# SH-SwitchNode-CT1_Shield.net
KiCad netlist of a schematic drawn in EAGLE
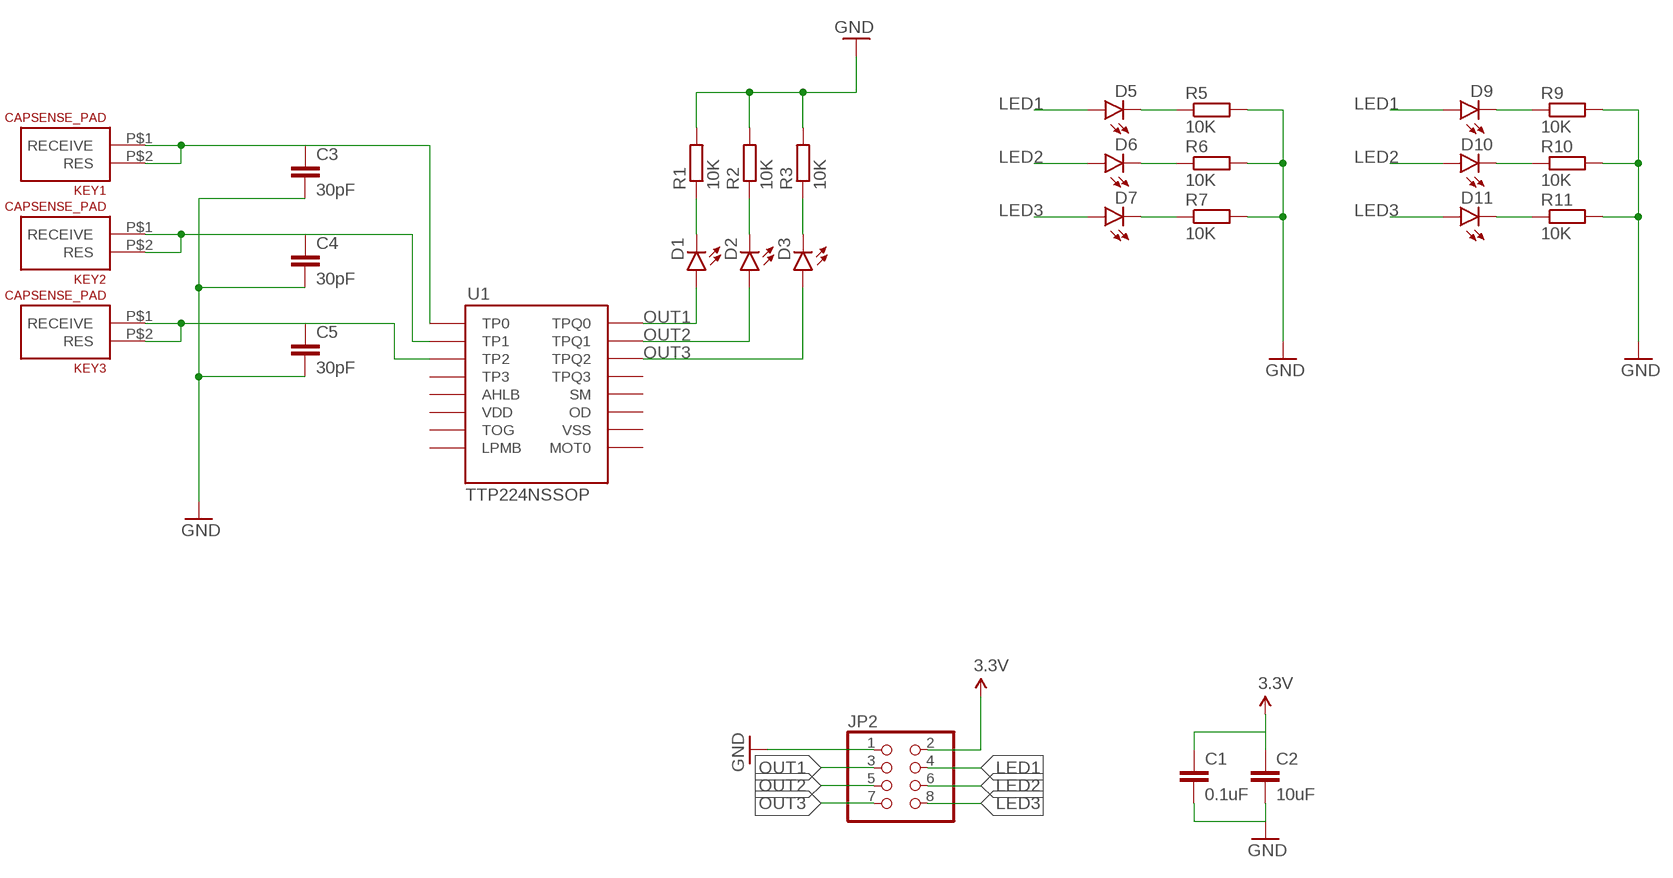
[diagram p0: schematic, sheet 1]

(export (version "E")
  (design (tool "Eeschema 10.0.6"))
  (components
    (comp (ref "C1")
      (value "0.1uF")
      (footprint "eagle-import:0805")
      (libsource (lib "eagle-import") (part "CAP0805"))
    )
    (comp (ref "C2")
      (value "10uF")
      (footprint "eagle-import:0805")
      (libsource (lib "eagle-import") (part "CAP0805"))
    )
    (comp (ref "C3")
      (value "30pF")
      (footprint "eagle-import:0805")
      (libsource (lib "eagle-import") (part "CAP0805"))
    )
    (comp (ref "C4")
      (value "30pF")
      (footprint "eagle-import:0805")
      (libsource (lib "eagle-import") (part "CAP0805"))
    )
    (comp (ref "C5")
      (value "30pF")
      (footprint "eagle-import:0805")
      (libsource (lib "eagle-import") (part "CAP0805"))
    )
    (comp (ref "D1")
      (value "LED1206-BOTTOM")
      (footprint "eagle-import:LED-1206-BOTTOM")
      (libsource (lib "eagle-import") (part "LED1206-BOTTOM"))
    )
    (comp (ref "D2")
      (value "LED1206-BOTTOM")
      (footprint "eagle-import:LED-1206-BOTTOM")
      (libsource (lib "eagle-import") (part "LED1206-BOTTOM"))
    )
    (comp (ref "D3")
      (value "LED1206-BOTTOM")
      (footprint "eagle-import:LED-1206-BOTTOM")
      (libsource (lib "eagle-import") (part "LED1206-BOTTOM"))
    )
    (comp (ref "D5")
      (value "LED1206-BOTTOM")
      (footprint "eagle-import:LED-1206-BOTTOM")
      (libsource (lib "eagle-import") (part "LED1206-BOTTOM"))
    )
    (comp (ref "D6")
      (value "LED1206-BOTTOM")
      (footprint "eagle-import:LED-1206-BOTTOM")
      (libsource (lib "eagle-import") (part "LED1206-BOTTOM"))
    )
    (comp (ref "D7")
      (value "LED1206-BOTTOM")
      (footprint "eagle-import:LED-1206-BOTTOM")
      (libsource (lib "eagle-import") (part "LED1206-BOTTOM"))
    )
    (comp (ref "D9")
      (value "LED1206-BOTTOM")
      (footprint "eagle-import:LED-1206-BOTTOM")
      (libsource (lib "eagle-import") (part "LED1206-BOTTOM"))
    )
    (comp (ref "D10")
      (value "LED1206-BOTTOM")
      (footprint "eagle-import:LED-1206-BOTTOM")
      (libsource (lib "eagle-import") (part "LED1206-BOTTOM"))
    )
    (comp (ref "D11")
      (value "LED1206-BOTTOM")
      (footprint "eagle-import:LED-1206-BOTTOM")
      (libsource (lib "eagle-import") (part "LED1206-BOTTOM"))
    )
    (comp (ref "JP2")
      (value "PINHD-2X4")
      (footprint "eagle-import:2X04")
      (libsource (lib "eagle-import") (part "PINHD-2X4"))
    )
    (comp (ref "KEY1")
      (value "CAPSENSE_PAD")
      (footprint "eagle-import:CAPSENSE_PAD")
      (libsource (lib "eagle-import") (part "CAPSENSE_PAD"))
    )
    (comp (ref "KEY2")
      (value "CAPSENSE_PAD")
      (footprint "eagle-import:CAPSENSE_PAD")
      (libsource (lib "eagle-import") (part "CAPSENSE_PAD"))
    )
    (comp (ref "KEY3")
      (value "CAPSENSE_PAD")
      (footprint "eagle-import:CAPSENSE_PAD")
      (libsource (lib "eagle-import") (part "CAPSENSE_PAD"))
    )
    (comp (ref "R1")
      (value "10K")
      (footprint "eagle-import:R0805")
      (libsource (lib "eagle-import") (part "R-EU_R0805"))
    )
    (comp (ref "R2")
      (value "10K")
      (footprint "eagle-import:R0805")
      (libsource (lib "eagle-import") (part "R-EU_R0805"))
    )
    (comp (ref "R3")
      (value "10K")
      (footprint "eagle-import:R0805")
      (libsource (lib "eagle-import") (part "R-EU_R0805"))
    )
    (comp (ref "R5")
      (value "10K")
      (footprint "eagle-import:R0805")
      (libsource (lib "eagle-import") (part "R-EU_R0805"))
    )
    (comp (ref "R6")
      (value "10K")
      (footprint "eagle-import:R0805")
      (libsource (lib "eagle-import") (part "R-EU_R0805"))
    )
    (comp (ref "R7")
      (value "10K")
      (footprint "eagle-import:R0805")
      (libsource (lib "eagle-import") (part "R-EU_R0805"))
    )
    (comp (ref "R9")
      (value "10K")
      (footprint "eagle-import:R0805")
      (libsource (lib "eagle-import") (part "R-EU_R0805"))
    )
    (comp (ref "R10")
      (value "10K")
      (footprint "eagle-import:R0805")
      (libsource (lib "eagle-import") (part "R-EU_R0805"))
    )
    (comp (ref "R11")
      (value "10K")
      (footprint "eagle-import:R0805")
      (libsource (lib "eagle-import") (part "R-EU_R0805"))
    )
    (comp (ref "U1")
      (value "TTP224NSSOP")
      (footprint "eagle-import:SSOP16")
      (libsource (lib "eagle-import") (part "TTP224NSSOP"))
    )
  )
  (nets
    (net (code "1") (name "/VDD") (class "Default")
      (node (ref "U1") (pin "6") (pinfunction "VDD_6") (pintype "power_in"))
    )
    (net (code "2") (name "/VSS") (class "Default")
      (node (ref "U1") (pin "10") (pinfunction "VSS_10") (pintype "power_in"))
    )
    (net (code "3") (name "3.3V") (class "Default")
      (node (ref "C1") (pin "1") (pinfunction "1_1") (pintype "passive"))
      (node (ref "C2") (pin "1") (pinfunction "1_1") (pintype "passive"))
      (node (ref "JP2") (pin "2") (pinfunction "2_2") (pintype "passive"))
    )
    (net (code "4") (name "GND") (class "Default")
      (node (ref "C1") (pin "2") (pinfunction "2_2") (pintype "passive"))
      (node (ref "C2") (pin "2") (pinfunction "2_2") (pintype "passive"))
      (node (ref "C3") (pin "2") (pinfunction "2_2") (pintype "passive"))
      (node (ref "C4") (pin "2") (pinfunction "2_2") (pintype "passive"))
      (node (ref "C5") (pin "2") (pinfunction "2_2") (pintype "passive"))
      (node (ref "JP2") (pin "1") (pinfunction "1_1") (pintype "passive"))
      (node (ref "R1") (pin "2") (pinfunction "2_2") (pintype "passive"))
      (node (ref "R10") (pin "2") (pinfunction "2_2") (pintype "passive"))
      (node (ref "R11") (pin "2") (pinfunction "2_2") (pintype "passive"))
      (node (ref "R2") (pin "2") (pinfunction "2_2") (pintype "passive"))
      (node (ref "R3") (pin "2") (pinfunction "2_2") (pintype "passive"))
      (node (ref "R5") (pin "2") (pinfunction "2_2") (pintype "passive"))
      (node (ref "R6") (pin "2") (pinfunction "2_2") (pintype "passive"))
      (node (ref "R7") (pin "2") (pinfunction "2_2") (pintype "passive"))
      (node (ref "R9") (pin "2") (pinfunction "2_2") (pintype "passive"))
    )
    (net (code "5") (name "LED1") (class "Default")
      (node (ref "D5") (pin "A") (pinfunction "A_A") (pintype "passive"))
      (node (ref "D9") (pin "A") (pinfunction "A_A") (pintype "passive"))
      (node (ref "JP2") (pin "4") (pinfunction "4_4") (pintype "passive"))
    )
    (net (code "6") (name "LED2") (class "Default")
      (node (ref "D10") (pin "A") (pinfunction "A_A") (pintype "passive"))
      (node (ref "D6") (pin "A") (pinfunction "A_A") (pintype "passive"))
      (node (ref "JP2") (pin "6") (pinfunction "6_6") (pintype "passive"))
    )
    (net (code "7") (name "LED3") (class "Default")
      (node (ref "D11") (pin "A") (pinfunction "A_A") (pintype "passive"))
      (node (ref "D7") (pin "A") (pinfunction "A_A") (pintype "passive"))
      (node (ref "JP2") (pin "8") (pinfunction "8_8") (pintype "passive"))
    )
    (net (code "8") (name "Net-(D1-PadC)") (class "Default")
      (node (ref "D1") (pin "C") (pinfunction "C_C") (pintype "passive"))
      (node (ref "R1") (pin "1") (pinfunction "1_1") (pintype "passive"))
    )
    (net (code "9") (name "Net-(D2-PadC)") (class "Default")
      (node (ref "D2") (pin "C") (pinfunction "C_C") (pintype "passive"))
      (node (ref "R2") (pin "1") (pinfunction "1_1") (pintype "passive"))
    )
    (net (code "10") (name "Net-(D3-PadC)") (class "Default")
      (node (ref "D3") (pin "C") (pinfunction "C_C") (pintype "passive"))
      (node (ref "R3") (pin "1") (pinfunction "1_1") (pintype "passive"))
    )
    (net (code "11") (name "Net-(D5-PadC)") (class "Default")
      (node (ref "D5") (pin "C") (pinfunction "C_C") (pintype "passive"))
      (node (ref "R5") (pin "1") (pinfunction "1_1") (pintype "passive"))
    )
    (net (code "12") (name "Net-(D6-PadC)") (class "Default")
      (node (ref "D6") (pin "C") (pinfunction "C_C") (pintype "passive"))
      (node (ref "R6") (pin "1") (pinfunction "1_1") (pintype "passive"))
    )
    (net (code "13") (name "Net-(D7-PadC)") (class "Default")
      (node (ref "D7") (pin "C") (pinfunction "C_C") (pintype "passive"))
      (node (ref "R7") (pin "1") (pinfunction "1_1") (pintype "passive"))
    )
    (net (code "14") (name "Net-(D9-PadC)") (class "Default")
      (node (ref "D9") (pin "C") (pinfunction "C_C") (pintype "passive"))
      (node (ref "R9") (pin "1") (pinfunction "1_1") (pintype "passive"))
    )
    (net (code "15") (name "Net-(D10-PadC)") (class "Default")
      (node (ref "D10") (pin "C") (pinfunction "C_C") (pintype "passive"))
      (node (ref "R10") (pin "1") (pinfunction "1_1") (pintype "passive"))
    )
    (net (code "16") (name "Net-(D11-PadC)") (class "Default")
      (node (ref "D11") (pin "C") (pinfunction "C_C") (pintype "passive"))
      (node (ref "R11") (pin "1") (pinfunction "1_1") (pintype "passive"))
    )
    (net (code "17") (name "Net-(KEY1-RECEIVE)") (class "Default")
      (node (ref "C3") (pin "1") (pinfunction "1_1") (pintype "passive"))
      (node (ref "KEY1") (pin "P$1") (pinfunction "RECEIVE_P$1") (pintype "bidirectional"))
      (node (ref "KEY1") (pin "P$2") (pinfunction "RES_P$2") (pintype "bidirectional"))
      (node (ref "U1") (pin "1") (pinfunction "TP0_1") (pintype "bidirectional"))
    )
    (net (code "18") (name "Net-(KEY2-RECEIVE)") (class "Default")
      (node (ref "C4") (pin "1") (pinfunction "1_1") (pintype "passive"))
      (node (ref "KEY2") (pin "P$1") (pinfunction "RECEIVE_P$1") (pintype "bidirectional"))
      (node (ref "KEY2") (pin "P$2") (pinfunction "RES_P$2") (pintype "bidirectional"))
      (node (ref "U1") (pin "2") (pinfunction "TP1_2") (pintype "bidirectional"))
    )
    (net (code "19") (name "Net-(KEY3-RECEIVE)") (class "Default")
      (node (ref "C5") (pin "1") (pinfunction "1_1") (pintype "passive"))
      (node (ref "KEY3") (pin "P$1") (pinfunction "RECEIVE_P$1") (pintype "bidirectional"))
      (node (ref "KEY3") (pin "P$2") (pinfunction "RES_P$2") (pintype "bidirectional"))
      (node (ref "U1") (pin "3") (pinfunction "TP2_3") (pintype "bidirectional"))
    )
    (net (code "20") (name "OUT1") (class "Default")
      (node (ref "D1") (pin "A") (pinfunction "A_A") (pintype "passive"))
      (node (ref "JP2") (pin "3") (pinfunction "3_3") (pintype "passive"))
      (node (ref "U1") (pin "16") (pinfunction "TPQ0_16") (pintype "output"))
    )
    (net (code "21") (name "OUT2") (class "Default")
      (node (ref "D2") (pin "A") (pinfunction "A_A") (pintype "passive"))
      (node (ref "JP2") (pin "5") (pinfunction "5_5") (pintype "passive"))
      (node (ref "U1") (pin "15") (pinfunction "TPQ1_15") (pintype "output"))
    )
    (net (code "22") (name "OUT3") (class "Default")
      (node (ref "D3") (pin "A") (pinfunction "A_A") (pintype "passive"))
      (node (ref "JP2") (pin "7") (pinfunction "7_7") (pintype "passive"))
      (node (ref "U1") (pin "14") (pinfunction "TPQ2_14") (pintype "output"))
    )
    (net (code "23") (name "unconnected-(U1-AHLB-Pad5)") (class "Default")
      (node (ref "U1") (pin "5") (pinfunction "AHLB_5") (pintype "bidirectional"))
    )
    (net (code "24") (name "unconnected-(U1-LPMB-Pad8)") (class "Default")
      (node (ref "U1") (pin "8") (pinfunction "LPMB_8") (pintype "bidirectional"))
    )
    (net (code "25") (name "unconnected-(U1-MOT0-Pad9)") (class "Default")
      (node (ref "U1") (pin "9") (pinfunction "MOT0_9") (pintype "bidirectional"))
    )
    (net (code "26") (name "unconnected-(U1-OD-Pad11)") (class "Default")
      (node (ref "U1") (pin "11") (pinfunction "OD_11") (pintype "bidirectional"))
    )
    (net (code "27") (name "unconnected-(U1-SM-Pad12)") (class "Default")
      (node (ref "U1") (pin "12") (pinfunction "SM_12") (pintype "bidirectional"))
    )
    (net (code "28") (name "unconnected-(U1-TOG-Pad7)") (class "Default")
      (node (ref "U1") (pin "7") (pinfunction "TOG_7") (pintype "bidirectional"))
    )
    (net (code "29") (name "unconnected-(U1-TP3-Pad4)") (class "Default")
      (node (ref "U1") (pin "4") (pinfunction "TP3_4") (pintype "bidirectional"))
    )
    (net (code "30") (name "unconnected-(U1-TPQ3-Pad13)") (class "Default")
      (node (ref "U1") (pin "13") (pinfunction "TPQ3_13") (pintype "output"))
    )
  )
)
